# toplevel.net
KiCad netlist of a schematic drawn in Altium Designer
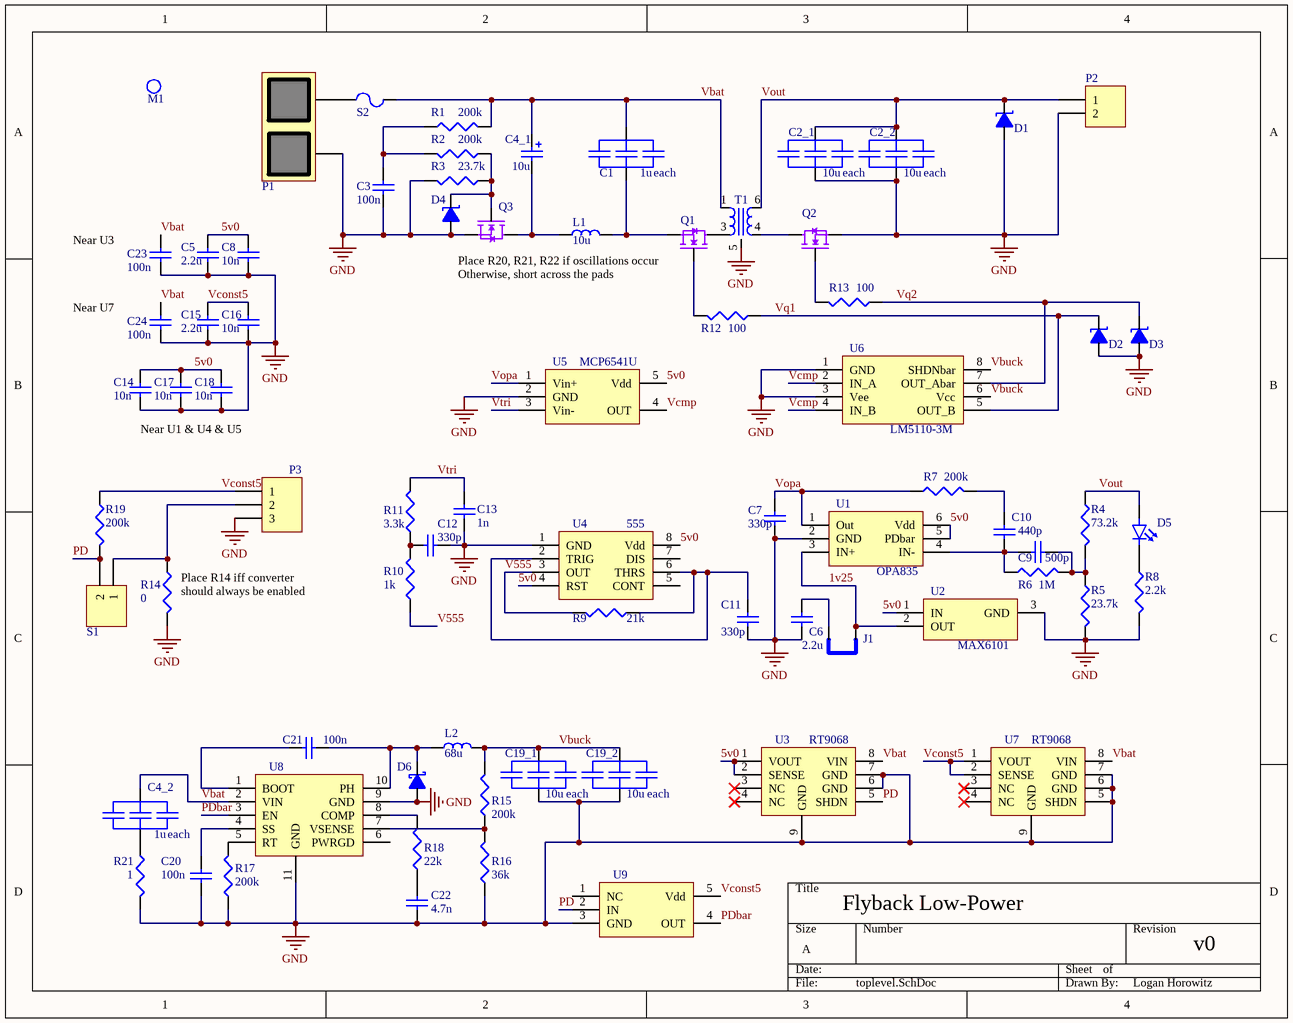
[diagram p0: toplevel.SchDoc]

(export (version "E")
  (design (tool "Eeschema 10.0.6"))
  (components
    (comp (ref "C1")
      (value "1u")
      (footprint "tricap_0805")
      (fields (field (name "Comment") "TriCap"))
      (libsource (lib "Components") (part "TriCap"))
    )
    (comp (ref "C2_1")
      (value "10u")
      (footprint "tricap_0603")
      (fields (field (name "Comment") "TriCap"))
      (libsource (lib "Components") (part "TriCap"))
    )
    (comp (ref "C2_2")
      (value "10u")
      (footprint "tricap_0603")
      (fields (field (name "Comment") "TriCap"))
      (libsource (lib "Components") (part "TriCap"))
    )
    (comp (ref "C3")
      (value "100n")
      (footprint "SMD0603_cap")
      (description "Ceramic Chip Capacitor")
      (fields (field (name "Comment") "Cap"))
      (libsource (lib "Components") (part "Capacitor Ceramic"))
    )
    (comp (ref "C4_1")
      (value "10u")
      (footprint "cap_radial_d")
      (description "Polarized Capacitor (Surface Mount)")
      (fields (field (name "Comment") "Cap"))
      (libsource (lib "Components") (part "Capacitor Polarized"))
    )
    (comp (ref "C4_2")
      (value "1u")
      (footprint "tricap_0805")
      (fields (field (name "Comment") "TriCap"))
      (libsource (lib "Components") (part "TriCap"))
    )
    (comp (ref "C5")
      (value "2.2u")
      (footprint "SMD0603_cap")
      (description "Ceramic Chip Capacitor")
      (fields (field (name "Comment") "Cap"))
      (libsource (lib "Components") (part "Capacitor Ceramic"))
    )
    (comp (ref "C6")
      (value "2.2u")
      (footprint "SMD0603_cap")
      (description "Ceramic Chip Capacitor")
      (fields (field (name "Comment") "Cap"))
      (libsource (lib "Components") (part "Capacitor Ceramic"))
    )
    (comp (ref "C7")
      (value "330p")
      (footprint "SMD0603_cap")
      (description "Ceramic Chip Capacitor")
      (fields (field (name "Comment") "Cap"))
      (libsource (lib "Components") (part "Capacitor Ceramic"))
    )
    (comp (ref "C8")
      (value "10n")
      (footprint "SMD0603_cap")
      (description "Ceramic Chip Capacitor")
      (fields (field (name "Comment") "Cap"))
      (libsource (lib "Components") (part "Capacitor Ceramic"))
    )
    (comp (ref "C9")
      (value "500p")
      (footprint "SMD0603_cap")
      (description "Ceramic Chip Capacitor")
      (fields (field (name "Comment") "Cap"))
      (libsource (lib "Components") (part "Capacitor Ceramic"))
    )
    (comp (ref "C10")
      (value "440p")
      (footprint "SMD0603_cap")
      (description "Ceramic Chip Capacitor")
      (fields (field (name "Comment") "Cap"))
      (libsource (lib "Components") (part "Capacitor Ceramic"))
    )
    (comp (ref "C11")
      (value "330p")
      (footprint "SMD0603_cap")
      (description "Ceramic Chip Capacitor")
      (fields (field (name "Comment") "Cap"))
      (libsource (lib "Components") (part "Capacitor Ceramic"))
    )
    (comp (ref "C12")
      (value "330p")
      (footprint "SMD0603_cap")
      (description "Ceramic Chip Capacitor")
      (fields (field (name "Comment") "Cap"))
      (libsource (lib "Components") (part "Capacitor Ceramic"))
    )
    (comp (ref "C13")
      (value "1n")
      (footprint "SMD0603_cap")
      (description "Ceramic Chip Capacitor")
      (fields (field (name "Comment") "Cap"))
      (libsource (lib "Components") (part "Capacitor Ceramic"))
    )
    (comp (ref "C14")
      (value "10n")
      (footprint "SMD0603_cap")
      (description "Ceramic Chip Capacitor")
      (fields (field (name "Comment") "Cap"))
      (libsource (lib "Components") (part "Capacitor Ceramic"))
    )
    (comp (ref "C15")
      (value "2.2u")
      (footprint "SMD0603_cap")
      (description "Ceramic Chip Capacitor")
      (fields (field (name "Comment") "Cap"))
      (libsource (lib "Components") (part "Capacitor Ceramic"))
    )
    (comp (ref "C16")
      (value "10n")
      (footprint "SMD0603_cap")
      (description "Ceramic Chip Capacitor")
      (fields (field (name "Comment") "Cap"))
      (libsource (lib "Components") (part "Capacitor Ceramic"))
    )
    (comp (ref "C17")
      (value "10n")
      (footprint "SMD0603_cap")
      (description "Ceramic Chip Capacitor")
      (fields (field (name "Comment") "Cap"))
      (libsource (lib "Components") (part "Capacitor Ceramic"))
    )
    (comp (ref "C18")
      (value "10n")
      (footprint "SMD0603_cap")
      (description "Ceramic Chip Capacitor")
      (fields (field (name "Comment") "Cap"))
      (libsource (lib "Components") (part "Capacitor Ceramic"))
    )
    (comp (ref "C19_1")
      (value "10u")
      (footprint "tricap_0603")
      (fields (field (name "Comment") "TriCap"))
      (libsource (lib "Components") (part "TriCap"))
    )
    (comp (ref "C19_2")
      (value "10u")
      (footprint "tricap_0603")
      (fields (field (name "Comment") "TriCap"))
      (libsource (lib "Components") (part "TriCap"))
    )
    (comp (ref "C20")
      (value "100n")
      (footprint "SMD0603_cap")
      (description "Ceramic Chip Capacitor")
      (fields (field (name "Comment") "Cap"))
      (libsource (lib "Components") (part "Capacitor Ceramic"))
    )
    (comp (ref "C21")
      (value "100n")
      (footprint "SMD0603_cap")
      (description "Ceramic Chip Capacitor")
      (fields (field (name "Comment") "Cap"))
      (libsource (lib "Components") (part "Capacitor Ceramic"))
    )
    (comp (ref "C22")
      (value "4.7n")
      (footprint "SMD0603_cap")
      (description "Ceramic Chip Capacitor")
      (fields (field (name "Comment") "Cap"))
      (libsource (lib "Components") (part "Capacitor Ceramic"))
    )
    (comp (ref "C23")
      (value "100n")
      (footprint "SMD0603_cap")
      (description "Ceramic Chip Capacitor")
      (fields (field (name "Comment") "Cap"))
      (libsource (lib "Components") (part "Capacitor Ceramic"))
    )
    (comp (ref "C24")
      (value "100n")
      (footprint "SMD0603_cap")
      (description "Ceramic Chip Capacitor")
      (fields (field (name "Comment") "Cap"))
      (libsource (lib "Components") (part "Capacitor Ceramic"))
    )
    (comp (ref "D1") (value "Zener") (footprint "SOD-323F") (libsource (lib "Components") (part "Zener")))
    (comp (ref "D2") (value "Zener") (footprint "SOD-323F") (libsource (lib "Components") (part "Zener")))
    (comp (ref "D3") (value "Zener") (footprint "SOD-323F") (libsource (lib "Components") (part "Zener")))
    (comp (ref "D4") (value "Zener") (footprint "SOD-323F") (libsource (lib "Components") (part "Zener")))
    (comp (ref "D5")
      (value "LED")
      (footprint "SMD0603 POLARIZED")
      (libsource (lib "Components") (part "LED"))
    )
    (comp (ref "D6") (value "Shottky") (footprint "sod-128") (libsource (lib "Components") (part "Shottky")))
    (comp (ref "J1") (value "Jumper") (footprint "jumper") (libsource (lib "Components") (part "Jumper")))
    (comp (ref "L1")
      (value "10u")
      (footprint "Nonstandard_10uH")
      (description "Inductor")
      (fields (field (name "PUBLISHER") "Altium Limited"))
      (libsource (lib "Components") (part "Inductor"))
    )
    (comp (ref "L2")
      (value "68u")
      (footprint "Nonstandard_68uH")
      (description "Inductor")
      (fields (field (name "PUBLISHER") "Altium Limited"))
      (libsource (lib "Components") (part "Inductor"))
    )
    (comp (ref "M1")
      (value "MountHole")
      (footprint "MountHole_M3")
      (libsource (lib "Components") (part "MountHole"))
    )
    (comp (ref "P1")
      (value "Microfit 2x1")
      (footprint "Microfit 2x1")
      (libsource (lib "Components") (part "Microfit 2x1"))
    )
    (comp (ref "P2")
      (value "Header")
      (footprint "Header 2x1")
      (description "Header, 2-Pin")
      (libsource (lib "Components") (part "Header 2x1"))
    )
    (comp (ref "P3")
      (value "Header")
      (footprint "HEADER 3X1")
      (description "Header, 2-Pin")
      (libsource (lib "Components") (part "Header 3x1"))
    )
    (comp (ref "Q1")
      (value "GaN PowerFET")
      (footprint "GaN Bumped Die")
      (libsource (lib "Components") (part "GaN PowerFET"))
    )
    (comp (ref "Q2")
      (value "GaN PowerFET")
      (footprint "GaN Bumped Die")
      (libsource (lib "Components") (part "GaN PowerFET"))
    )
    (comp (ref "Q3")
      (value "GaN PowerFET")
      (footprint "GaN Bumped Die")
      (libsource (lib "Components") (part "GaN PowerFET"))
    )
    (comp (ref "R1")
      (value "200k")
      (footprint "SMD0603")
      (description "Resistor")
      (fields (field (name "Comment") "Res"))
      (libsource (lib "Components") (part "Resistor"))
    )
    (comp (ref "R2")
      (value "200k")
      (footprint "SMD0603")
      (description "Resistor")
      (fields (field (name "Comment") "Res"))
      (libsource (lib "Components") (part "Resistor"))
    )
    (comp (ref "R3")
      (value "23.7k")
      (footprint "SMD0603")
      (description "Resistor")
      (fields (field (name "Comment") "Res"))
      (libsource (lib "Components") (part "Resistor"))
    )
    (comp (ref "R4")
      (value "73.2k")
      (footprint "SMD0603")
      (description "Resistor")
      (fields (field (name "Comment") "Res"))
      (libsource (lib "Components") (part "Resistor"))
    )
    (comp (ref "R5")
      (value "23.7k")
      (footprint "SMD0603")
      (description "Resistor")
      (fields (field (name "Comment") "Res"))
      (libsource (lib "Components") (part "Resistor"))
    )
    (comp (ref "R6")
      (value "1M")
      (footprint "SMD0603")
      (description "Resistor")
      (fields (field (name "Comment") "Res"))
      (libsource (lib "Components") (part "Resistor"))
    )
    (comp (ref "R7")
      (value "200k")
      (footprint "SMD0603")
      (description "Resistor")
      (fields (field (name "Comment") "Res"))
      (libsource (lib "Components") (part "Resistor"))
    )
    (comp (ref "R8")
      (value "2.2k")
      (footprint "SMD0603")
      (description "Resistor")
      (fields (field (name "Comment") "Res"))
      (libsource (lib "Components") (part "Resistor"))
    )
    (comp (ref "R9")
      (value "21k")
      (footprint "SMD0603")
      (description "Resistor")
      (fields (field (name "Comment") "Res"))
      (libsource (lib "Components") (part "Resistor"))
    )
    (comp (ref "R10")
      (value "1k")
      (footprint "SMD0603")
      (description "Resistor")
      (fields (field (name "Comment") "Res"))
      (libsource (lib "Components") (part "Resistor"))
    )
    (comp (ref "R11")
      (value "3.3k")
      (footprint "SMD0603")
      (description "Resistor")
      (fields (field (name "Comment") "Res"))
      (libsource (lib "Components") (part "Resistor"))
    )
    (comp (ref "R12")
      (value "100")
      (footprint "SMD0603")
      (description "Resistor")
      (fields (field (name "Comment") "Res"))
      (libsource (lib "Components") (part "Resistor"))
    )
    (comp (ref "R13")
      (value "100")
      (footprint "SMD0603")
      (description "Resistor")
      (fields (field (name "Comment") "Res"))
      (libsource (lib "Components") (part "Resistor"))
    )
    (comp (ref "R14")
      (value "0")
      (footprint "SMD0603")
      (description "Resistor")
      (fields (field (name "Comment") "Res"))
      (libsource (lib "Components") (part "Resistor"))
    )
    (comp (ref "R15")
      (value "200k")
      (footprint "SMD0603")
      (description "Resistor")
      (fields (field (name "Comment") "Res"))
      (libsource (lib "Components") (part "Resistor"))
    )
    (comp (ref "R16")
      (value "36k")
      (footprint "SMD0603")
      (description "Resistor")
      (fields (field (name "Comment") "Res"))
      (libsource (lib "Components") (part "Resistor"))
    )
    (comp (ref "R17")
      (value "200k")
      (footprint "SMD0603")
      (description "Resistor")
      (fields (field (name "Comment") "Res"))
      (libsource (lib "Components") (part "Resistor"))
    )
    (comp (ref "R18")
      (value "22k")
      (footprint "SMD0603")
      (description "Resistor")
      (fields (field (name "Comment") "Res"))
      (libsource (lib "Components") (part "Resistor"))
    )
    (comp (ref "R19")
      (value "200k")
      (footprint "SMD0603")
      (description "Resistor")
      (fields (field (name "Comment") "Res"))
      (libsource (lib "Components") (part "Resistor"))
    )
    (comp (ref "R21")
      (value "1")
      (footprint "SMD0603")
      (description "Resistor")
      (fields (field (name "Comment") "Res"))
      (libsource (lib "Components") (part "Resistor"))
    )
    (comp (ref "S1")
      (value "Header")
      (footprint "Header 2x1")
      (description "Header, 2-Pin")
      (libsource (lib "") (part "Header 2x1_1"))
    )
    (comp (ref "S2")
      (value "Fuse_SMD")
      (footprint "smd1206")
      (libsource (lib "Components") (part "Fuse_SMD"))
    )
    (comp (ref "T1")
      (value "Transformer")
      (footprint "P1408")
      (libsource (lib "Components") (part "Transformer"))
    )
    (comp (ref "U1") (value "OPA835") (footprint "SOT23-6L") (libsource (lib "Components") (part "OPA835")))
    (comp (ref "U2") (value "MAX6101") (footprint "sot23") (libsource (lib "Components") (part "MAX6101")))
    (comp (ref "U3") (value "RT9068") (footprint "soic-8_pad") (libsource (lib "Components") (part "RT9068")))
    (comp (ref "U4") (value "555") (footprint "SOIC8") (libsource (lib "Components") (part "555")))
    (comp (ref "U5")
      (value "MCP6541U")
      (footprint "SOT23-5Lead")
      (libsource (lib "Components") (part "MCP6541U"))
    )
    (comp (ref "U6")
      (value "LM5110-3M")
      (footprint "soic8")
      (libsource (lib "Components") (part "LM5110-3M"))
    )
    (comp (ref "U7") (value "RT9068") (footprint "soic-8_pad") (libsource (lib "Components") (part "RT9068")))
    (comp (ref "U8")
      (value "TPS54260")
      (footprint "MSSOP-10")
      (libsource (lib "Components") (part "TPS54260"))
    )
    (comp (ref "U9")
      (value "NC7SZ04")
      (footprint "SOT23-5Lead")
      (libsource (lib "Components") (part "NC7SZ04"))
    )
  )
  (nets
    (net (code "1") (name "/1v25") (class "Default")
      (node (ref "J1") (pin "1") (pinfunction "1_1") (pintype "passive"))
      (node (ref "U1") (pin "3") (pinfunction "IN+_3") (pintype "passive"))
      (node (ref "U2") (pin "2") (pinfunction "OUT_2") (pintype "passive"))
    )
    (net (code "2") (name "/5v0") (class "Default")
      (node (ref "C14") (pin "1") (pinfunction "1_1") (pintype "passive"))
      (node (ref "C17") (pin "1") (pinfunction "1_1") (pintype "passive"))
      (node (ref "C18") (pin "1") (pinfunction "1_1") (pintype "passive"))
      (node (ref "C5") (pin "1") (pinfunction "1_1") (pintype "passive"))
      (node (ref "C8") (pin "1") (pinfunction "1_1") (pintype "passive"))
      (node (ref "U1") (pin "5") (pinfunction "PDbar_5") (pintype "passive"))
      (node (ref "U1") (pin "6") (pinfunction "Vdd_6") (pintype "passive"))
      (node (ref "U2") (pin "1") (pinfunction "IN_1") (pintype "passive"))
      (node (ref "U3") (pin "1") (pinfunction "VOUT_1") (pintype "passive"))
      (node (ref "U3") (pin "2") (pinfunction "SENSE_2") (pintype "passive"))
      (node (ref "U4") (pin "4") (pinfunction "RST_4") (pintype "passive"))
      (node (ref "U4") (pin "8") (pinfunction "Vdd_8") (pintype "passive"))
      (node (ref "U5") (pin "5") (pinfunction "Vdd_5") (pintype "passive"))
    )
    (net (code "3") (name "/PD") (class "Default")
      (node (ref "R19") (pin "2") (pinfunction "2_2") (pintype "passive"))
      (node (ref "S1") (pin "2") (pinfunction "2_2") (pintype "passive"))
      (node (ref "U3") (pin "5") (pinfunction "SHDN_5") (pintype "passive"))
      (node (ref "U9") (pin "2") (pinfunction "IN_2") (pintype "passive"))
    )
    (net (code "4") (name "/PDbar") (class "Default")
      (node (ref "U8") (pin "3") (pinfunction "EN_3") (pintype "passive"))
      (node (ref "U9") (pin "4") (pinfunction "OUT_4") (pintype "passive"))
    )
    (net (code "5") (name "/V555") (class "Default")
      (node (ref "R10") (pin "1") (pinfunction "1_1") (pintype "passive"))
      (node (ref "R9") (pin "2") (pinfunction "2_2") (pintype "passive"))
      (node (ref "U4") (pin "3") (pinfunction "OUT_3") (pintype "passive"))
    )
    (net (code "6") (name "/Vbat") (class "Default")
      (node (ref "C1") (pin "2") (pinfunction "2_2") (pintype "passive"))
      (node (ref "C23") (pin "2") (pinfunction "2_2") (pintype "passive"))
      (node (ref "C24") (pin "2") (pinfunction "2_2") (pintype "passive"))
      (node (ref "C4_1") (pin "1") (pinfunction "1_1") (pintype "passive"))
      (node (ref "C4_2") (pin "2") (pinfunction "2_2") (pintype "passive"))
      (node (ref "R1") (pin "2") (pinfunction "2_2") (pintype "passive"))
      (node (ref "S2") (pin "2") (pintype "passive"))
      (node (ref "T1") (pin "1") (pinfunction "Source_1") (pintype "passive"))
      (node (ref "U3") (pin "8") (pinfunction "VIN_8") (pintype "passive"))
      (node (ref "U7") (pin "8") (pinfunction "VIN_8") (pintype "passive"))
      (node (ref "U8") (pin "2") (pinfunction "VIN_2") (pintype "passive"))
    )
    (net (code "7") (name "/Vbuck") (class "Default")
      (node (ref "C19_1") (pin "2") (pinfunction "2_2") (pintype "passive"))
      (node (ref "C19_2") (pin "2") (pinfunction "2_2") (pintype "passive"))
      (node (ref "L2") (pin "2") (pinfunction "Source_2") (pintype "passive"))
      (node (ref "R15") (pin "2") (pinfunction "2_2") (pintype "passive"))
      (node (ref "U6") (pin "6") (pinfunction "Vcc_6") (pintype "passive"))
      (node (ref "U6") (pin "8") (pinfunction "SHDNbar_8") (pintype "passive"))
    )
    (net (code "8") (name "/Vcmp") (class "Default")
      (node (ref "U5") (pin "4") (pinfunction "OUT_4") (pintype "passive"))
      (node (ref "U6") (pin "2") (pinfunction "IN_A_2") (pintype "passive"))
      (node (ref "U6") (pin "4") (pinfunction "IN_B_4") (pintype "passive"))
    )
    (net (code "9") (name "/Vconst5") (class "Default")
      (node (ref "C15") (pin "1") (pinfunction "1_1") (pintype "passive"))
      (node (ref "C16") (pin "1") (pinfunction "1_1") (pintype "passive"))
      (node (ref "P3") (pin "1") (pinfunction "1_1") (pintype "passive"))
      (node (ref "R19") (pin "1") (pinfunction "1_1") (pintype "passive"))
      (node (ref "U7") (pin "1") (pinfunction "VOUT_1") (pintype "passive"))
      (node (ref "U7") (pin "2") (pinfunction "SENSE_2") (pintype "passive"))
      (node (ref "U9") (pin "5") (pinfunction "Vdd_5") (pintype "passive"))
    )
    (net (code "10") (name "/Vopa") (class "Default")
      (node (ref "C7") (pin "1") (pinfunction "1_1") (pintype "passive"))
      (node (ref "R7") (pin "1") (pinfunction "1_1") (pintype "passive"))
      (node (ref "U1") (pin "1") (pinfunction "Out_1") (pintype "passive"))
      (node (ref "U5") (pin "1") (pinfunction "Vin+_1") (pintype "passive"))
    )
    (net (code "11") (name "/Vout") (class "Default")
      (node (ref "C2_1") (pin "2") (pinfunction "2_2") (pintype "passive"))
      (node (ref "C2_2") (pin "2") (pinfunction "2_2") (pintype "passive"))
      (node (ref "D1") (pin "K") (pinfunction "2_K") (pintype "passive"))
      (node (ref "D5") (pin "1") (pinfunction "Anode_(+)_1") (pintype "passive"))
      (node (ref "P2") (pin "1") (pinfunction "1_1") (pintype "passive"))
      (node (ref "R4") (pin "1") (pinfunction "1_1") (pintype "passive"))
      (node (ref "T1") (pin "6") (pinfunction "A_6") (pintype "passive"))
    )
    (net (code "12") (name "/Vq1") (class "Default")
      (node (ref "D2") (pin "K") (pinfunction "2_K") (pintype "passive"))
      (node (ref "R12") (pin "1") (pinfunction "1_1") (pintype "passive"))
      (node (ref "U6") (pin "5") (pinfunction "OUT_B_5") (pintype "passive"))
    )
    (net (code "13") (name "/Vq2") (class "Default")
      (node (ref "D3") (pin "K") (pinfunction "2_K") (pintype "passive"))
      (node (ref "R13") (pin "1") (pinfunction "1_1") (pintype "passive"))
      (node (ref "U6") (pin "7") (pinfunction "OUT_Abar_7") (pintype "passive"))
    )
    (net (code "14") (name "/Vtri") (class "Default")
      (node (ref "C13") (pin "1") (pinfunction "1_1") (pintype "passive"))
      (node (ref "R11") (pin "2") (pinfunction "2_2") (pintype "passive"))
      (node (ref "U5") (pin "3") (pinfunction "Vin-_3") (pintype "passive"))
    )
    (net (code "15") (name "GND") (class "Default")
      (node (ref "C11") (pin "1") (pinfunction "1_1") (pintype "passive"))
      (node (ref "C12") (pin "1") (pinfunction "1_1") (pintype "passive"))
      (node (ref "C13") (pin "2") (pinfunction "2_2") (pintype "passive"))
      (node (ref "C14") (pin "2") (pinfunction "2_2") (pintype "passive"))
      (node (ref "C15") (pin "2") (pinfunction "2_2") (pintype "passive"))
      (node (ref "C16") (pin "2") (pinfunction "2_2") (pintype "passive"))
      (node (ref "C17") (pin "2") (pinfunction "2_2") (pintype "passive"))
      (node (ref "C18") (pin "2") (pinfunction "2_2") (pintype "passive"))
      (node (ref "C19_1") (pin "1") (pinfunction "1_1") (pintype "passive"))
      (node (ref "C19_2") (pin "1") (pinfunction "1_1") (pintype "passive"))
      (node (ref "C20") (pin "2") (pinfunction "2_2") (pintype "passive"))
      (node (ref "C22") (pin "2") (pinfunction "2_2") (pintype "passive"))
      (node (ref "C23") (pin "1") (pinfunction "1_1") (pintype "passive"))
      (node (ref "C24") (pin "1") (pinfunction "1_1") (pintype "passive"))
      (node (ref "C2_1") (pin "1") (pinfunction "1_1") (pintype "passive"))
      (node (ref "C2_2") (pin "1") (pinfunction "1_1") (pintype "passive"))
      (node (ref "C3") (pin "1") (pinfunction "1_1") (pintype "passive"))
      (node (ref "C5") (pin "2") (pinfunction "2_2") (pintype "passive"))
      (node (ref "C6") (pin "2") (pinfunction "2_2") (pintype "passive"))
      (node (ref "C7") (pin "2") (pinfunction "2_2") (pintype "passive"))
      (node (ref "C8") (pin "2") (pinfunction "2_2") (pintype "passive"))
      (node (ref "D1") (pin "A") (pintype "passive"))
      (node (ref "D2") (pin "A") (pintype "passive"))
      (node (ref "D3") (pin "A") (pintype "passive"))
      (node (ref "D4") (pin "A") (pintype "passive"))
      (node (ref "D6") (pin "A") (pinfunction "1_A") (pintype "passive"))
      (node (ref "P1") (pin "2") (pintype "passive"))
      (node (ref "P2") (pin "2") (pinfunction "2_2") (pintype "passive"))
      (node (ref "P3") (pin "3") (pinfunction "3_3") (pintype "passive"))
      (node (ref "Q2") (pin "S") (pintype "passive"))
      (node (ref "Q3") (pin "S") (pintype "passive"))
      (node (ref "R14") (pin "2") (pinfunction "2_2") (pintype "passive"))
      (node (ref "R16") (pin "1") (pinfunction "1_1") (pintype "passive"))
      (node (ref "R17") (pin "1") (pinfunction "1_1") (pintype "passive"))
      (node (ref "R21") (pin "2") (pinfunction "2_2") (pintype "passive"))
      (node (ref "R3") (pin "2") (pinfunction "2_2") (pintype "passive"))
      (node (ref "R5") (pin "2") (pinfunction "2_2") (pintype "passive"))
      (node (ref "R8") (pin "2") (pinfunction "2_2") (pintype "passive"))
      (node (ref "T1") (pin "5") (pinfunction "A_5") (pintype "passive"))
      (node (ref "U1") (pin "2") (pinfunction "GND_2") (pintype "passive"))
      (node (ref "U2") (pin "3") (pinfunction "GND_3") (pintype "passive"))
      (node (ref "U3") (pin "6") (pinfunction "GND_6") (pintype "passive"))
      (node (ref "U3") (pin "7") (pinfunction "GND_7") (pintype "passive"))
      (node (ref "U3") (pin "9") (pinfunction "GND_9") (pintype "passive"))
      (node (ref "U4") (pin "1") (pinfunction "GND_1") (pintype "passive"))
      (node (ref "U5") (pin "2") (pinfunction "GND_2") (pintype "passive"))
      (node (ref "U6") (pin "1") (pinfunction "GND_1") (pintype "passive"))
      (node (ref "U6") (pin "3") (pinfunction "Vee_3") (pintype "passive"))
      (node (ref "U7") (pin "5") (pinfunction "SHDN_5") (pintype "passive"))
      (node (ref "U7") (pin "6") (pinfunction "GND_6") (pintype "passive"))
      (node (ref "U7") (pin "7") (pinfunction "GND_7") (pintype "passive"))
      (node (ref "U7") (pin "9") (pinfunction "GND_9") (pintype "passive"))
      (node (ref "U8") (pin "11") (pinfunction "GND_11") (pintype "passive"))
      (node (ref "U8") (pin "9") (pinfunction "GND_9") (pintype "passive"))
      (node (ref "U9") (pin "3") (pinfunction "GND_3") (pintype "passive"))
    )
    (net (code "16") (name "Net-(C1-Pad1)") (class "Default")
      (node (ref "C1") (pin "1") (pinfunction "1_1") (pintype "passive"))
      (node (ref "L1") (pin "2") (pinfunction "Source_2") (pintype "passive"))
      (node (ref "Q1") (pin "S") (pintype "passive"))
    )
    (net (code "17") (name "Net-(C3-Pad2)") (class "Default")
      (node (ref "C3") (pin "2") (pinfunction "2_2") (pintype "passive"))
      (node (ref "R1") (pin "1") (pinfunction "1_1") (pintype "passive"))
      (node (ref "R2") (pin "2") (pinfunction "2_2") (pintype "passive"))
    )
    (net (code "18") (name "Net-(C4_1-Pad2)") (class "Default")
      (node (ref "C4_1") (pin "2") (pinfunction "2_2") (pintype "passive"))
      (node (ref "L1") (pin "1") (pinfunction "Source_1") (pintype "passive"))
      (node (ref "Q3") (pin "D") (pintype "passive"))
    )
    (net (code "19") (name "Net-(C4_2-Pad1)") (class "Default")
      (node (ref "C4_2") (pin "1") (pinfunction "1_1") (pintype "passive"))
      (node (ref "R21") (pin "1") (pinfunction "1_1") (pintype "passive"))
    )
    (net (code "20") (name "Net-(C6-Pad1)") (class "Default")
      (node (ref "C6") (pin "1") (pinfunction "1_1") (pintype "passive"))
      (node (ref "J1") (pin "2") (pinfunction "2_2") (pintype "passive"))
    )
    (net (code "21") (name "Net-(C9-Pad1)") (class "Default")
      (node (ref "C9") (pin "1") (pinfunction "1_1") (pintype "passive"))
      (node (ref "R4") (pin "2") (pinfunction "2_2") (pintype "passive"))
      (node (ref "R5") (pin "1") (pinfunction "1_1") (pintype "passive"))
      (node (ref "R6") (pin "2") (pinfunction "2_2") (pintype "passive"))
    )
    (net (code "22") (name "Net-(C10-Pad1)") (class "Default")
      (node (ref "C10") (pin "1") (pinfunction "1_1") (pintype "passive"))
      (node (ref "R7") (pin "2") (pinfunction "2_2") (pintype "passive"))
    )
    (net (code "23") (name "Net-(C12-Pad2)") (class "Default")
      (node (ref "C12") (pin "2") (pinfunction "2_2") (pintype "passive"))
      (node (ref "R10") (pin "2") (pinfunction "2_2") (pintype "passive"))
      (node (ref "R11") (pin "1") (pinfunction "1_1") (pintype "passive"))
    )
    (net (code "24") (name "Net-(C22-Pad1)") (class "Default")
      (node (ref "C22") (pin "1") (pinfunction "1_1") (pintype "passive"))
      (node (ref "R18") (pin "1") (pinfunction "1_1") (pintype "passive"))
    )
    (net (code "25") (name "Net-(D4-2)") (class "Default")
      (node (ref "D4") (pin "K") (pinfunction "2_K") (pintype "passive"))
      (node (ref "Q3") (pin "G") (pintype "passive"))
      (node (ref "R2") (pin "1") (pinfunction "1_1") (pintype "passive"))
      (node (ref "R3") (pin "1") (pinfunction "1_1") (pintype "passive"))
    )
    (net (code "26") (name "Net-(D5-Cathode_(-))") (class "Default")
      (node (ref "D5") (pin "2") (pinfunction "Cathode_(-)_2") (pintype "passive"))
      (node (ref "R8") (pin "1") (pinfunction "1_1") (pintype "passive"))
    )
    (net (code "27") (name "Net-(D6-2)") (class "Default")
      (node (ref "C21") (pin "2") (pinfunction "2_2") (pintype "passive"))
      (node (ref "D6") (pin "K") (pinfunction "2_K") (pintype "passive"))
      (node (ref "L2") (pin "1") (pinfunction "Source_1") (pintype "passive"))
      (node (ref "U8") (pin "10") (pinfunction "PH_10") (pintype "passive"))
    )
    (net (code "28") (name "Net-(P1-Pad1)") (class "Default")
      (node (ref "P1") (pin "1") (pintype "passive"))
      (node (ref "S2") (pin "1") (pintype "passive"))
    )
    (net (code "29") (name "Net-(P3-Pad2)") (class "Default")
      (node (ref "P3") (pin "2") (pinfunction "2_2") (pintype "passive"))
      (node (ref "R14") (pin "1") (pinfunction "1_1") (pintype "passive"))
      (node (ref "S1") (pin "1") (pinfunction "1_1") (pintype "passive"))
    )
    (net (code "30") (name "Net-(Q1-PadD)") (class "Default")
      (node (ref "Q1") (pin "D") (pintype "passive"))
      (node (ref "T1") (pin "3") (pinfunction "Source_3") (pintype "passive"))
    )
    (net (code "31") (name "Net-(Q1-PadG)") (class "Default")
      (node (ref "Q1") (pin "G") (pintype "passive"))
      (node (ref "R12") (pin "2") (pinfunction "2_2") (pintype "passive"))
    )
    (net (code "32") (name "Net-(Q2-PadD)") (class "Default")
      (node (ref "Q2") (pin "D") (pintype "passive"))
      (node (ref "T1") (pin "4") (pinfunction "A_4") (pintype "passive"))
    )
    (net (code "33") (name "Net-(Q2-PadG)") (class "Default")
      (node (ref "Q2") (pin "G") (pintype "passive"))
      (node (ref "R13") (pin "2") (pinfunction "2_2") (pintype "passive"))
    )
    (net (code "34") (name "Net-(U1-IN-)") (class "Default")
      (node (ref "C10") (pin "2") (pinfunction "2_2") (pintype "passive"))
      (node (ref "C9") (pin "2") (pinfunction "2_2") (pintype "passive"))
      (node (ref "R6") (pin "1") (pinfunction "1_1") (pintype "passive"))
      (node (ref "U1") (pin "4") (pinfunction "IN-_4") (pintype "passive"))
    )
    (net (code "35") (name "Net-(U4-THRS)") (class "Default")
      (node (ref "C11") (pin "2") (pinfunction "2_2") (pintype "passive"))
      (node (ref "R9") (pin "1") (pinfunction "1_1") (pintype "passive"))
      (node (ref "U4") (pin "2") (pinfunction "TRIG_2") (pintype "passive"))
      (node (ref "U4") (pin "6") (pinfunction "THRS_6") (pintype "passive"))
    )
    (net (code "36") (name "Net-(U8-BOOT)") (class "Default")
      (node (ref "C21") (pin "1") (pinfunction "1_1") (pintype "passive"))
      (node (ref "U8") (pin "1") (pinfunction "BOOT_1") (pintype "passive"))
    )
    (net (code "37") (name "Net-(U8-COMP)") (class "Default")
      (node (ref "R18") (pin "2") (pinfunction "2_2") (pintype "passive"))
      (node (ref "U8") (pin "8") (pinfunction "COMP_8") (pintype "passive"))
    )
    (net (code "38") (name "Net-(U8-RT)") (class "Default")
      (node (ref "R17") (pin "2") (pinfunction "2_2") (pintype "passive"))
      (node (ref "U8") (pin "5") (pinfunction "RT_5") (pintype "passive"))
    )
    (net (code "39") (name "Net-(U8-SS)") (class "Default")
      (node (ref "C20") (pin "1") (pinfunction "1_1") (pintype "passive"))
      (node (ref "U8") (pin "4") (pinfunction "SS_4") (pintype "passive"))
    )
    (net (code "40") (name "Net-(U8-VSENSE)") (class "Default")
      (node (ref "R15") (pin "1") (pinfunction "1_1") (pintype "passive"))
      (node (ref "R16") (pin "2") (pinfunction "2_2") (pintype "passive"))
      (node (ref "U8") (pin "7") (pinfunction "VSENSE_7") (pintype "passive"))
    )
    (net (code "41") (name "unconnected-(U3-NC-Pad3)") (class "Default")
      (node (ref "U3") (pin "3") (pinfunction "NC_3") (pintype "passive+no_connect"))
    )
    (net (code "42") (name "unconnected-(U3-NC-Pad4)") (class "Default")
      (node (ref "U3") (pin "4") (pinfunction "NC_4") (pintype "passive+no_connect"))
    )
    (net (code "43") (name "unconnected-(U4-CONT-Pad5)") (class "Default")
      (node (ref "U4") (pin "5") (pinfunction "CONT_5") (pintype "passive"))
    )
    (net (code "44") (name "unconnected-(U4-DIS-Pad7)") (class "Default")
      (node (ref "U4") (pin "7") (pinfunction "DIS_7") (pintype "passive"))
    )
    (net (code "45") (name "unconnected-(U7-NC-Pad3)") (class "Default")
      (node (ref "U7") (pin "3") (pinfunction "NC_3") (pintype "passive+no_connect"))
    )
    (net (code "46") (name "unconnected-(U7-NC-Pad4)") (class "Default")
      (node (ref "U7") (pin "4") (pinfunction "NC_4") (pintype "passive+no_connect"))
    )
    (net (code "47") (name "unconnected-(U8-PWRGD-Pad6)") (class "Default")
      (node (ref "U8") (pin "6") (pinfunction "PWRGD_6") (pintype "passive"))
    )
    (net (code "48") (name "unconnected-(U9-NC-Pad1)") (class "Default")
      (node (ref "U9") (pin "1") (pinfunction "NC_1") (pintype "passive"))
    )
  )
)
